# ReflowCntrl.net
KiCad netlist of a schematic drawn in EAGLE
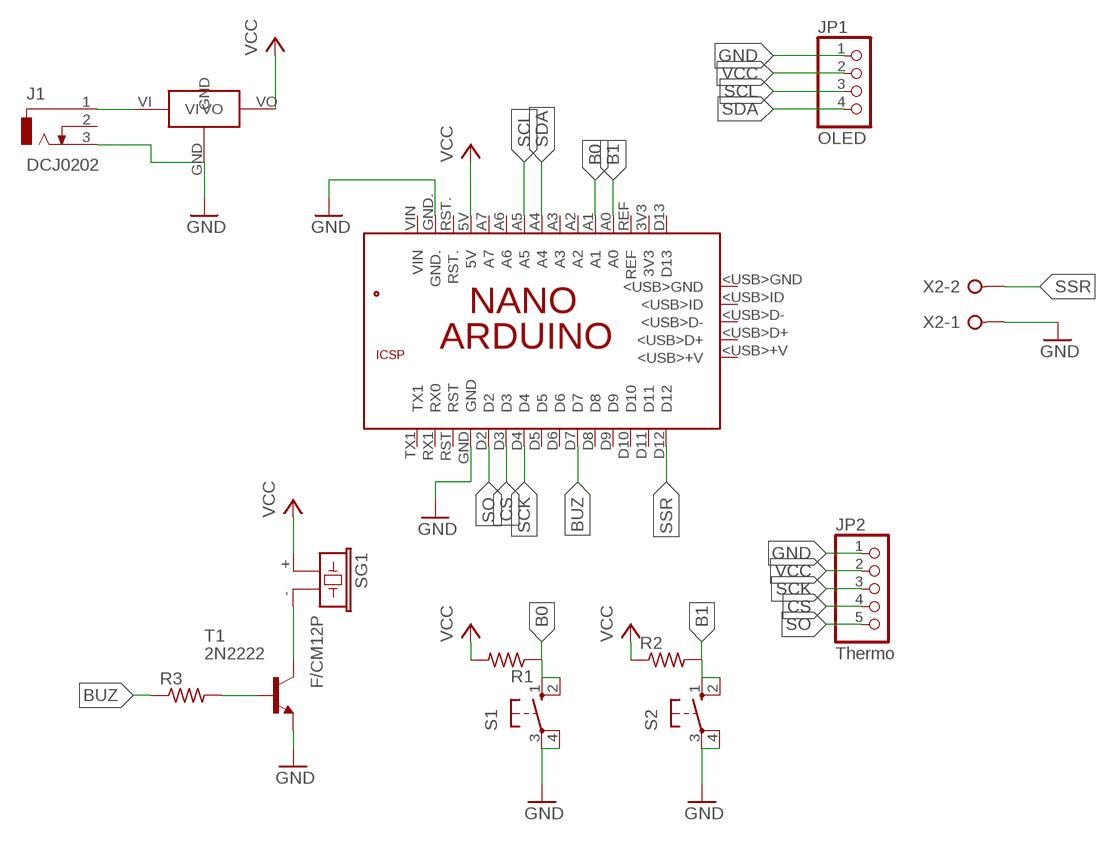
[diagram p0: schematic, sheet 1]

(export (version "E")
  (design (tool "Eeschema 10.0.6"))
  (components
    (comp (ref "J1")
      (value "DCJ0202")
      (footprint "eagle-import:DCJ0202")
      (libsource (lib "eagle-import") (part "DCJ0202"))
    )
    (comp (ref "JP1")
      (value "OLED")
      (footprint "eagle-import:1X04")
      (libsource (lib "eagle-import") (part "PINHD-1X4"))
    )
    (comp (ref "JP2")
      (value "Thermo")
      (footprint "eagle-import:1X05")
      (libsource (lib "eagle-import") (part "PINHD-1X5"))
    )
    (comp (ref "PCB1")
      (value "ARDUINO_NANO")
      (footprint "eagle-import:ARDUINO_NANO")
      (libsource (lib "eagle-import") (part "ARDUINO_NANO"))
    )
    (comp (ref "R1")
      (value "R-US_0207/10")
      (footprint "eagle-import:0207_10")
      (libsource (lib "eagle-import") (part "R-US_0207/10"))
    )
    (comp (ref "R2")
      (value "R-US_0207/10")
      (footprint "eagle-import:0207_10")
      (libsource (lib "eagle-import") (part "R-US_0207/10"))
    )
    (comp (ref "R3")
      (value "R-US_0207/10")
      (footprint "eagle-import:0207_10")
      (libsource (lib "eagle-import") (part "R-US_0207/10"))
    )
    (comp (ref "S1")
      (value "10-XX")
      (footprint "eagle-import:B3F-10XX")
      (fields (field (name "MPN") "B3F-1000"))
      (libsource (lib "eagle-import") (part "10-XX"))
    )
    (comp (ref "S2")
      (value "10-XX")
      (footprint "eagle-import:B3F-10XX")
      (fields (field (name "MPN") "B3F-1000"))
      (libsource (lib "eagle-import") (part "10-XX"))
    )
    (comp (ref "SG1")
      (value "F/CM12P")
      (footprint "eagle-import:F_CM12P")
      (libsource (lib "eagle-import") (part "F/CM12P"))
    )
    (comp (ref "T1")
      (value "2N2222")
      (footprint "eagle-import:TO92-EBC-OVAL")
      (libsource (lib "eagle-import") (part "2N2222"))
    )
    (comp (ref "U$1")
      (value "7805-TO220V")
      (footprint "eagle-import:TO220AV")
      (libsource (lib "eagle-import") (part "7805-TO220V"))
    )
    (comp (ref "X2")
      (value "W237-02P")
      (footprint "eagle-import:W237-132")
      (libsource (lib "eagle-import") (part "W237-02P"))
    )
  )
  (nets
    (net (code "1") (name "B0") (class "Default")
      (node (ref "PCB1") (pin "A1") (pinfunction "A1_A1") (pintype "bidirectional"))
      (node (ref "R1") (pin "1") (pinfunction "1_1") (pintype "passive"))
      (node (ref "S1") (pin "1") (pinfunction "S_1") (pintype "passive"))
      (node (ref "S1") (pin "2") (pinfunction "S1_2") (pintype "passive"))
    )
    (net (code "2") (name "B1") (class "Default")
      (node (ref "PCB1") (pin "A0") (pinfunction "A0_A0") (pintype "bidirectional"))
      (node (ref "R2") (pin "2") (pinfunction "2_2") (pintype "passive"))
      (node (ref "S2") (pin "1") (pinfunction "S_1") (pintype "passive"))
      (node (ref "S2") (pin "2") (pinfunction "S1_2") (pintype "passive"))
    )
    (net (code "3") (name "BUZ") (class "Default")
      (node (ref "PCB1") (pin "D7") (pinfunction "D7_D7") (pintype "bidirectional"))
      (node (ref "R3") (pin "1") (pinfunction "1_1") (pintype "passive"))
    )
    (net (code "4") (name "CS") (class "Default")
      (node (ref "JP2") (pin "4") (pinfunction "4_4") (pintype "passive"))
      (node (ref "PCB1") (pin "D3") (pinfunction "D3_D3") (pintype "bidirectional"))
    )
    (net (code "5") (name "GND") (class "Default")
      (node (ref "J1") (pin "3") (pinfunction "3_3") (pintype "passive"))
      (node (ref "JP1") (pin "1") (pinfunction "1_1") (pintype "passive"))
      (node (ref "JP2") (pin "1") (pinfunction "1_1") (pintype "passive"))
      (node (ref "PCB1") (pin "GND") (pinfunction "GND_GND") (pintype "bidirectional"))
      (node (ref "PCB1") (pin "GND.") (pinfunction "GND._GND.") (pintype "bidirectional"))
      (node (ref "S1") (pin "3") (pinfunction "P_3") (pintype "passive"))
      (node (ref "S1") (pin "4") (pinfunction "P1_4") (pintype "passive"))
      (node (ref "S2") (pin "3") (pinfunction "P_3") (pintype "passive"))
      (node (ref "S2") (pin "4") (pinfunction "P1_4") (pintype "passive"))
      (node (ref "T1") (pin "E") (pinfunction "E_E") (pintype "passive"))
      (node (ref "U$1") (pin "GND") (pinfunction "GND_GND") (pintype "bidirectional"))
      (node (ref "X2") (pin "1") (pinfunction "KL_1") (pintype "passive"))
    )
    (net (code "6") (name "Net-(J1-Pad1)") (class "Default")
      (node (ref "J1") (pin "1") (pinfunction "1_1") (pintype "passive"))
      (node (ref "U$1") (pin "VI") (pinfunction "VI_VI") (pintype "input"))
    )
    (net (code "7") (name "Net-(R3-Pad2)") (class "Default")
      (node (ref "R3") (pin "2") (pinfunction "2_2") (pintype "passive"))
      (node (ref "T1") (pin "B") (pinfunction "B_B") (pintype "passive"))
    )
    (net (code "8") (name "Net-(SG1-2)") (class "Default")
      (node (ref "SG1") (pin "-") (pinfunction "2_-") (pintype "passive"))
      (node (ref "T1") (pin "C") (pinfunction "C_C") (pintype "passive"))
    )
    (net (code "9") (name "SCK") (class "Default")
      (node (ref "JP2") (pin "3") (pinfunction "3_3") (pintype "passive"))
      (node (ref "PCB1") (pin "D4") (pinfunction "D4_D4") (pintype "bidirectional"))
    )
    (net (code "10") (name "SCL") (class "Default")
      (node (ref "JP1") (pin "3") (pinfunction "3_3") (pintype "passive"))
      (node (ref "PCB1") (pin "A5") (pinfunction "A5_A5") (pintype "bidirectional"))
    )
    (net (code "11") (name "SDA") (class "Default")
      (node (ref "JP1") (pin "4") (pinfunction "4_4") (pintype "passive"))
      (node (ref "PCB1") (pin "A4") (pinfunction "A4_A4") (pintype "bidirectional"))
    )
    (net (code "12") (name "SO") (class "Default")
      (node (ref "JP2") (pin "5") (pinfunction "5_5") (pintype "passive"))
      (node (ref "PCB1") (pin "D2") (pinfunction "D2_D2") (pintype "bidirectional"))
    )
    (net (code "13") (name "SSR") (class "Default")
      (node (ref "PCB1") (pin "D12") (pinfunction "D12_D12") (pintype "bidirectional"))
      (node (ref "X2") (pin "2") (pinfunction "KL_2") (pintype "passive"))
    )
    (net (code "14") (name "VCC") (class "Default")
      (node (ref "JP1") (pin "2") (pinfunction "2_2") (pintype "passive"))
      (node (ref "JP2") (pin "2") (pinfunction "2_2") (pintype "passive"))
      (node (ref "PCB1") (pin "5V") (pinfunction "5V_5V") (pintype "bidirectional"))
      (node (ref "R1") (pin "2") (pinfunction "2_2") (pintype "passive"))
      (node (ref "R2") (pin "1") (pinfunction "1_1") (pintype "passive"))
      (node (ref "SG1") (pin "+") (pinfunction "1_+") (pintype "passive"))
      (node (ref "U$1") (pin "VO") (pinfunction "VO_VO") (pintype "output"))
    )
    (net (code "15") (name "unconnected-(J1-Pad2)") (class "Default")
      (node (ref "J1") (pin "2") (pinfunction "2_2") (pintype "passive"))
    )
    (net (code "16") (name "unconnected-(PCB1-Pad3V3)") (class "Default")
      (node (ref "PCB1") (pin "3V3") (pinfunction "3V3_3V3") (pintype "bidirectional"))
    )
    (net (code "17") (name "unconnected-(PCB1-Pad5V.)") (class "Default")
      (node (ref "PCB1") (pin "5V.") (pinfunction "5V._5V.") (pintype "bidirectional"))
    )
    (net (code "18") (name "unconnected-(PCB1-Pad<USB>+V)") (class "Default")
      (node (ref "PCB1") (pin "<USB>+V") (pinfunction "<USB>+V_<USB>+V") (pintype "bidirectional"))
    )
    (net (code "19") (name "unconnected-(PCB1-Pad<USB>D+)") (class "Default")
      (node (ref "PCB1") (pin "<USB>D+") (pinfunction "<USB>D+_<USB>D+") (pintype "bidirectional"))
    )
    (net (code "20") (name "unconnected-(PCB1-Pad<USB>D-)") (class "Default")
      (node (ref "PCB1") (pin "<USB>D-") (pinfunction "<USB>D-_<USB>D-") (pintype "bidirectional"))
    )
    (net (code "21") (name "unconnected-(PCB1-Pad<USB>GND)") (class "Default")
      (node (ref "PCB1") (pin "<USB>GND") (pinfunction "<USB>GND_<USB>GND") (pintype "bidirectional"))
    )
    (net (code "22") (name "unconnected-(PCB1-Pad<USB>ID)") (class "Default")
      (node (ref "PCB1") (pin "<USB>ID") (pinfunction "<USB>ID_<USB>ID") (pintype "bidirectional"))
    )
    (net (code "23") (name "unconnected-(PCB1-PadA2)") (class "Default")
      (node (ref "PCB1") (pin "A2") (pinfunction "A2_A2") (pintype "bidirectional"))
    )
    (net (code "24") (name "unconnected-(PCB1-PadA3)") (class "Default")
      (node (ref "PCB1") (pin "A3") (pinfunction "A3_A3") (pintype "bidirectional"))
    )
    (net (code "25") (name "unconnected-(PCB1-PadA6)") (class "Default")
      (node (ref "PCB1") (pin "A6") (pinfunction "A6_A6") (pintype "bidirectional"))
    )
    (net (code "26") (name "unconnected-(PCB1-PadA7)") (class "Default")
      (node (ref "PCB1") (pin "A7") (pinfunction "A7_A7") (pintype "bidirectional"))
    )
    (net (code "27") (name "unconnected-(PCB1-PadD5)") (class "Default")
      (node (ref "PCB1") (pin "D5") (pinfunction "D5_D5") (pintype "bidirectional"))
    )
    (net (code "28") (name "unconnected-(PCB1-PadD6)") (class "Default")
      (node (ref "PCB1") (pin "D6") (pinfunction "D6_D6") (pintype "bidirectional"))
    )
    (net (code "29") (name "unconnected-(PCB1-PadD8)") (class "Default")
      (node (ref "PCB1") (pin "D8") (pinfunction "D8_D8") (pintype "bidirectional"))
    )
    (net (code "30") (name "unconnected-(PCB1-PadD9)") (class "Default")
      (node (ref "PCB1") (pin "D9") (pinfunction "D9_D9") (pintype "bidirectional"))
    )
    (net (code "31") (name "unconnected-(PCB1-PadD10)") (class "Default")
      (node (ref "PCB1") (pin "D10") (pinfunction "D10_D10") (pintype "bidirectional"))
    )
    (net (code "32") (name "unconnected-(PCB1-PadD11)") (class "Default")
      (node (ref "PCB1") (pin "D11") (pinfunction "D11_D11") (pintype "bidirectional"))
    )
    (net (code "33") (name "unconnected-(PCB1-PadD13)") (class "Default")
      (node (ref "PCB1") (pin "D13") (pinfunction "D13_D13") (pintype "bidirectional"))
    )
    (net (code "34") (name "unconnected-(PCB1-PadGND_)") (class "Default")
      (node (ref "PCB1") (pin "GND_") (pinfunction "GND__GND_") (pintype "bidirectional"))
    )
    (net (code "35") (name "unconnected-(PCB1-PadMISO)") (class "Default")
      (node (ref "PCB1") (pin "MISO") (pinfunction "MISO_MISO") (pintype "bidirectional"))
    )
    (net (code "36") (name "unconnected-(PCB1-PadMOSI)") (class "Default")
      (node (ref "PCB1") (pin "MOSI") (pinfunction "MOSI_MOSI") (pintype "bidirectional"))
    )
    (net (code "37") (name "unconnected-(PCB1-PadREF)") (class "Default")
      (node (ref "PCB1") (pin "REF") (pinfunction "REF_REF") (pintype "bidirectional"))
    )
    (net (code "38") (name "unconnected-(PCB1-PadRESET..)") (class "Default")
      (node (ref "PCB1") (pin "RESET..") (pinfunction "RESET.._RESET..") (pintype "bidirectional"))
    )
    (net (code "39") (name "unconnected-(PCB1-PadRST)") (class "Default")
      (node (ref "PCB1") (pin "RST") (pinfunction "RST_RST") (pintype "bidirectional"))
    )
    (net (code "40") (name "unconnected-(PCB1-PadRST.)") (class "Default")
      (node (ref "PCB1") (pin "RST.") (pinfunction "RST._RST.") (pintype "bidirectional"))
    )
    (net (code "41") (name "unconnected-(PCB1-PadSCK)") (class "Default")
      (node (ref "PCB1") (pin "SCK") (pinfunction "SCK_SCK") (pintype "bidirectional"))
    )
    (net (code "42") (name "unconnected-(PCB1-PadTX1)") (class "Default")
      (node (ref "PCB1") (pin "TX1") (pinfunction "TX1_TX1") (pintype "bidirectional"))
    )
    (net (code "43") (name "unconnected-(PCB1-PadVIN)") (class "Default")
      (node (ref "PCB1") (pin "VIN") (pinfunction "VIN_VIN") (pintype "bidirectional"))
    )
    (net (code "44") (name "unconnected-(PCB1-RX0-PadRX1)") (class "Default")
      (node (ref "PCB1") (pin "RX1") (pinfunction "RX0_RX1") (pintype "bidirectional"))
    )
  )
)
